# schematic.net
KiCad netlist of a schematic drawn in EasyEDA
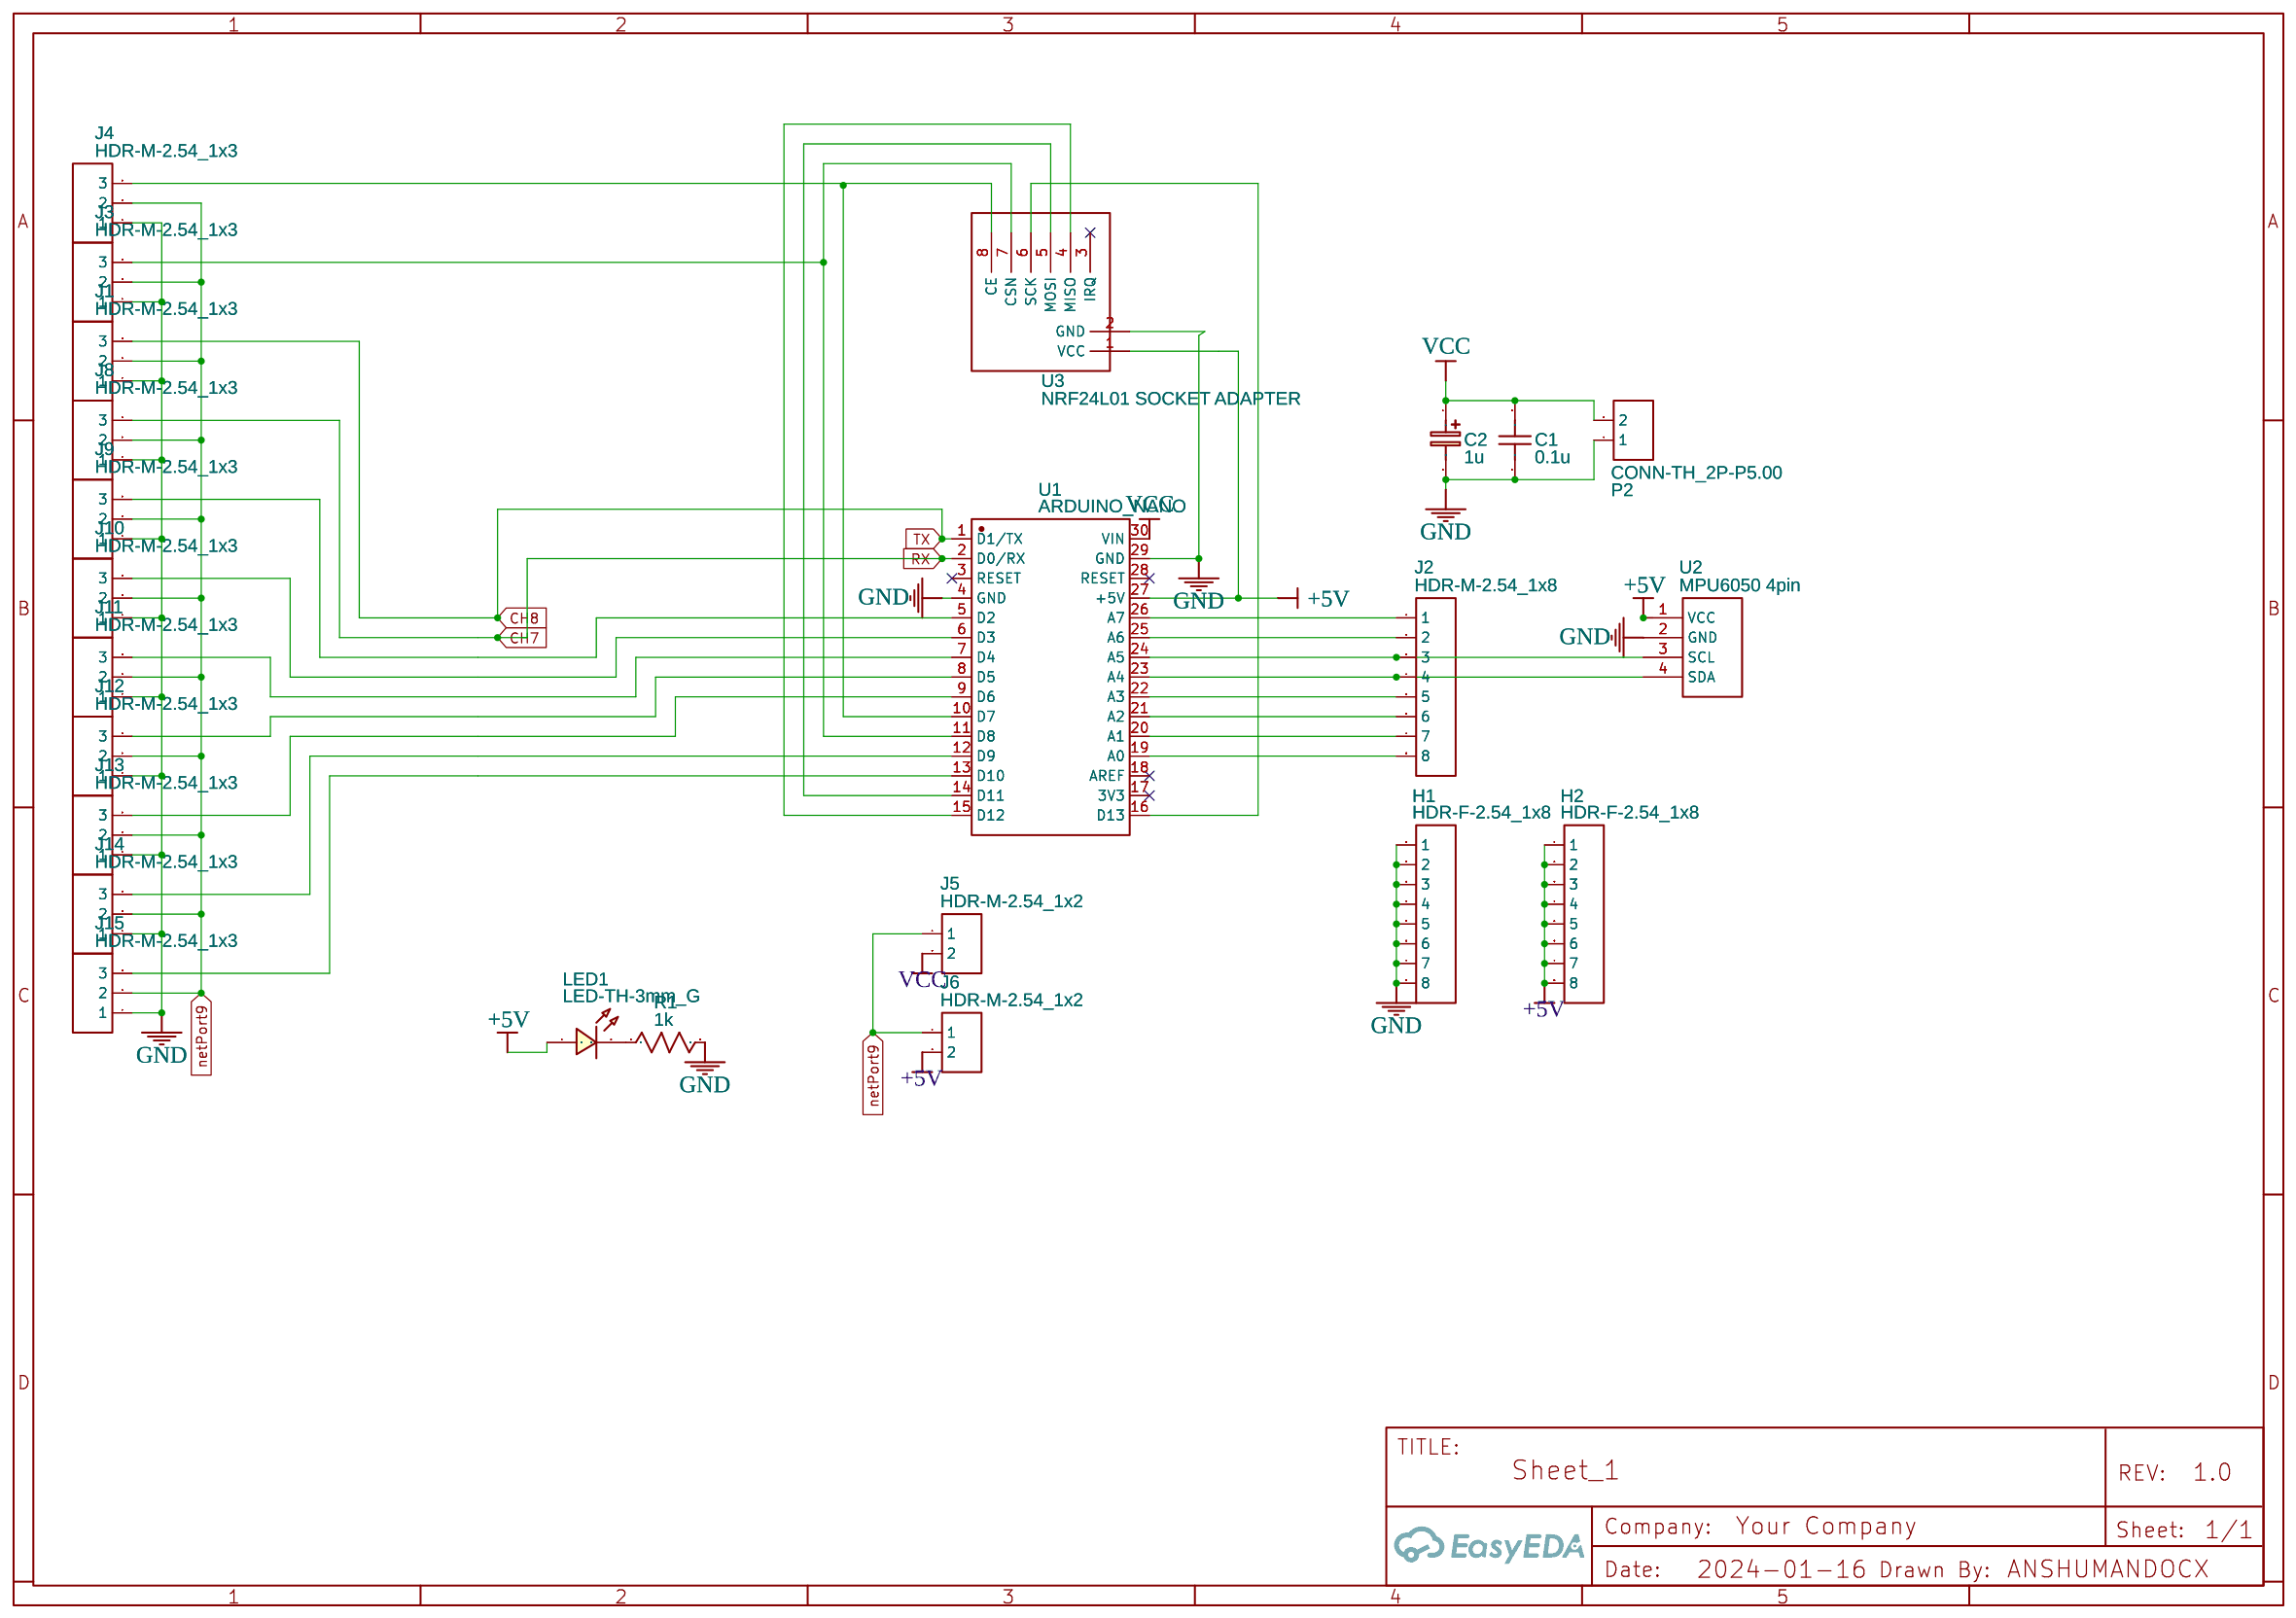
[diagram p0: schematic sheet]

(export (version "E")
  (design (tool "Eeschema 10.0.6"))
  (components
    (comp (ref "C1") (value "0.1u") (libsource (lib "") (part "C_0805_US")))
    (comp (ref "C2") (value "1u") (libsource (lib "") (part "CE_TH_D5.0×F2.0_EU")))
    (comp (ref "H1") (value "HDR-F-2.54_1x8") (libsource (lib "") (part "HDR-F-2.54_1x8")))
    (comp (ref "H2") (value "HDR-F-2.54_1x8") (libsource (lib "") (part "HDR-F-2.54_1x8")))
    (comp (ref "J1") (value "HDR-M-2.54_1x3") (libsource (lib "") (part "HDR-M-2.54_1x3")))
    (comp (ref "J2") (value "HDR-M-2.54_1x8") (libsource (lib "") (part "HDR-M-2.54_1x8")))
    (comp (ref "J3") (value "HDR-M-2.54_1x3") (libsource (lib "") (part "HDR-M-2.54_1x3")))
    (comp (ref "J4") (value "HDR-M-2.54_1x3") (libsource (lib "") (part "HDR-M-2.54_1x3")))
    (comp (ref "J5") (value "HDR-M-2.54_1x2") (libsource (lib "") (part "HDR-M-2.54_1x2")))
    (comp (ref "J6") (value "HDR-M-2.54_1x2") (libsource (lib "") (part "HDR-M-2.54_1x2")))
    (comp (ref "J8") (value "HDR-M-2.54_1x3") (libsource (lib "") (part "HDR-M-2.54_1x3")))
    (comp (ref "J9") (value "HDR-M-2.54_1x3") (libsource (lib "") (part "HDR-M-2.54_1x3")))
    (comp (ref "J10") (value "HDR-M-2.54_1x3") (libsource (lib "") (part "HDR-M-2.54_1x3")))
    (comp (ref "J11") (value "HDR-M-2.54_1x3") (libsource (lib "") (part "HDR-M-2.54_1x3")))
    (comp (ref "J12") (value "HDR-M-2.54_1x3") (libsource (lib "") (part "HDR-M-2.54_1x3")))
    (comp (ref "J13") (value "HDR-M-2.54_1x3") (libsource (lib "") (part "HDR-M-2.54_1x3")))
    (comp (ref "J14") (value "HDR-M-2.54_1x3") (libsource (lib "") (part "HDR-M-2.54_1x3")))
    (comp (ref "J15") (value "HDR-M-2.54_1x3") (libsource (lib "") (part "HDR-M-2.54_1x3")))
    (comp (ref "LED1")
      (value "LED-TH-3mm_G")
      (fields
        (field (name "Manufacturer Part") "204-10SYGD/S530-E3")
        (field (name "Manufacturer") "EVERLIGHT(台湾亿光)")
      )
      (libsource (lib "") (part "LED-TH-3mm_G"))
    )
    (comp (ref "P2") (value "CONN-TH_2P-P5.00") (libsource (lib "") (part "CONN-TH_2P-P5.00")))
    (comp (ref "R1") (value "1k") (libsource (lib "") (part "R_AXIAL-0.4_US")))
    (comp (ref "U1") (value "ARDUINO_NANO") (libsource (lib "") (part "ARDUINO_NANO")))
    (comp (ref "U2") (value "MPU6050 4pin") (libsource (lib "") (part "MPU6050 4pin")))
    (comp (ref "U3") (value "NRF24L01 SOCKET ADAPTER") (libsource (lib "") (part "NRF24L01 SOCKET ADAPTER")))
  )
  (nets
    (net (code "1") (name "+5V") (class "Default")
      (node (ref "H2") (pin "1") (pinfunction "1_1") (pintype "unspecified"))
      (node (ref "H2") (pin "2") (pinfunction "2_2") (pintype "unspecified"))
      (node (ref "H2") (pin "3") (pinfunction "3_3") (pintype "unspecified"))
      (node (ref "H2") (pin "4") (pinfunction "4_4") (pintype "unspecified"))
      (node (ref "H2") (pin "5") (pinfunction "5_5") (pintype "unspecified"))
      (node (ref "H2") (pin "6") (pinfunction "6_6") (pintype "unspecified"))
      (node (ref "H2") (pin "7") (pinfunction "7_7") (pintype "unspecified"))
      (node (ref "H2") (pin "8") (pinfunction "8_8") (pintype "unspecified"))
      (node (ref "J6") (pin "2") (pinfunction "2_2") (pintype "unspecified"))
      (node (ref "LED1") (pin "1") (pinfunction "1_1") (pintype "unspecified"))
      (node (ref "U1") (pin "27") (pinfunction "+5V_27") (pintype "unspecified"))
      (node (ref "U2") (pin "1") (pinfunction "VCC_1") (pintype "unspecified"))
      (node (ref "U3") (pin "1") (pinfunction "VCC_1") (pintype "unspecified"))
    )
    (net (code "2") (name "CH7") (class "Default")
      (node (ref "J8") (pin "3") (pinfunction "3_3") (pintype "input"))
      (node (ref "U1") (pin "2") (pinfunction "D0/RX_2") (pintype "unspecified"))
    )
    (net (code "3") (name "CH8") (class "Default")
      (node (ref "J1") (pin "3") (pinfunction "3_3") (pintype "input"))
      (node (ref "U1") (pin "1") (pinfunction "D1/TX_1") (pintype "unspecified"))
    )
    (net (code "4") (name "GND") (class "Default")
      (node (ref "C1") (pin "1") (pinfunction "1_1") (pintype "unspecified"))
      (node (ref "C2") (pin "2") (pinfunction "2_2") (pintype "unspecified"))
      (node (ref "H1") (pin "1") (pinfunction "1_1") (pintype "unspecified"))
      (node (ref "H1") (pin "2") (pinfunction "2_2") (pintype "unspecified"))
      (node (ref "H1") (pin "3") (pinfunction "3_3") (pintype "unspecified"))
      (node (ref "H1") (pin "4") (pinfunction "4_4") (pintype "unspecified"))
      (node (ref "H1") (pin "5") (pinfunction "5_5") (pintype "unspecified"))
      (node (ref "H1") (pin "6") (pinfunction "6_6") (pintype "unspecified"))
      (node (ref "H1") (pin "7") (pinfunction "7_7") (pintype "unspecified"))
      (node (ref "H1") (pin "8") (pinfunction "8_8") (pintype "unspecified"))
      (node (ref "J1") (pin "1") (pinfunction "1_1") (pintype "input"))
      (node (ref "J10") (pin "1") (pinfunction "1_1") (pintype "input"))
      (node (ref "J11") (pin "1") (pinfunction "1_1") (pintype "input"))
      (node (ref "J12") (pin "1") (pinfunction "1_1") (pintype "input"))
      (node (ref "J13") (pin "1") (pinfunction "1_1") (pintype "input"))
      (node (ref "J14") (pin "1") (pinfunction "1_1") (pintype "input"))
      (node (ref "J15") (pin "1") (pinfunction "1_1") (pintype "input"))
      (node (ref "J3") (pin "1") (pinfunction "1_1") (pintype "input"))
      (node (ref "J4") (pin "1") (pinfunction "1_1") (pintype "input"))
      (node (ref "J8") (pin "1") (pinfunction "1_1") (pintype "input"))
      (node (ref "J9") (pin "1") (pinfunction "1_1") (pintype "input"))
      (node (ref "P2") (pin "1") (pinfunction "1_1") (pintype "unspecified"))
      (node (ref "R1") (pin "2") (pinfunction "2_2") (pintype "unspecified"))
      (node (ref "U1") (pin "29") (pinfunction "GND_29") (pintype "unspecified"))
      (node (ref "U1") (pin "4") (pinfunction "GND_4") (pintype "unspecified"))
      (node (ref "U2") (pin "2") (pinfunction "GND_2") (pintype "unspecified"))
      (node (ref "U3") (pin "2") (pinfunction "GND_2") (pintype "unspecified"))
    )
    (net (code "5") (name "Net-(LED1-Pad2)") (class "Default")
      (node (ref "LED1") (pin "2") (pinfunction "2_2") (pintype "unspecified"))
      (node (ref "R1") (pin "1") (pinfunction "1_1") (pintype "unspecified"))
    )
    (net (code "6") (name "Net-(U1-A0)") (class "Default")
      (node (ref "J2") (pin "8") (pinfunction "8_8") (pintype "unspecified"))
      (node (ref "U1") (pin "19") (pinfunction "A0_19") (pintype "unspecified"))
    )
    (net (code "7") (name "Net-(U1-A1)") (class "Default")
      (node (ref "J2") (pin "7") (pinfunction "7_7") (pintype "unspecified"))
      (node (ref "U1") (pin "20") (pinfunction "A1_20") (pintype "unspecified"))
    )
    (net (code "8") (name "Net-(U1-A2)") (class "Default")
      (node (ref "J2") (pin "6") (pinfunction "6_6") (pintype "unspecified"))
      (node (ref "U1") (pin "21") (pinfunction "A2_21") (pintype "unspecified"))
    )
    (net (code "9") (name "Net-(U1-A3)") (class "Default")
      (node (ref "J2") (pin "5") (pinfunction "5_5") (pintype "unspecified"))
      (node (ref "U1") (pin "22") (pinfunction "A3_22") (pintype "unspecified"))
    )
    (net (code "10") (name "Net-(U1-A4)") (class "Default")
      (node (ref "J2") (pin "4") (pinfunction "4_4") (pintype "unspecified"))
      (node (ref "U1") (pin "23") (pinfunction "A4_23") (pintype "unspecified"))
      (node (ref "U2") (pin "4") (pinfunction "SDA_4") (pintype "unspecified"))
    )
    (net (code "11") (name "Net-(U1-A5)") (class "Default")
      (node (ref "J2") (pin "3") (pinfunction "3_3") (pintype "unspecified"))
      (node (ref "U1") (pin "24") (pinfunction "A5_24") (pintype "unspecified"))
      (node (ref "U2") (pin "3") (pinfunction "SCL_3") (pintype "unspecified"))
    )
    (net (code "12") (name "Net-(U1-A6)") (class "Default")
      (node (ref "J2") (pin "2") (pinfunction "2_2") (pintype "unspecified"))
      (node (ref "U1") (pin "25") (pinfunction "A6_25") (pintype "unspecified"))
    )
    (net (code "13") (name "Net-(U1-A7)") (class "Default")
      (node (ref "J2") (pin "1") (pinfunction "1_1") (pintype "unspecified"))
      (node (ref "U1") (pin "26") (pinfunction "A7_26") (pintype "unspecified"))
    )
    (net (code "14") (name "Net-(U1-D2)") (class "Default")
      (node (ref "J9") (pin "3") (pinfunction "3_3") (pintype "input"))
      (node (ref "U1") (pin "5") (pinfunction "D2_5") (pintype "unspecified"))
    )
    (net (code "15") (name "Net-(U1-D3)") (class "Default")
      (node (ref "J10") (pin "3") (pinfunction "3_3") (pintype "input"))
      (node (ref "U1") (pin "6") (pinfunction "D3_6") (pintype "unspecified"))
    )
    (net (code "16") (name "Net-(U1-D4)") (class "Default")
      (node (ref "J11") (pin "3") (pinfunction "3_3") (pintype "input"))
      (node (ref "U1") (pin "7") (pinfunction "D4_7") (pintype "unspecified"))
    )
    (net (code "17") (name "Net-(U1-D5)") (class "Default")
      (node (ref "J12") (pin "3") (pinfunction "3_3") (pintype "input"))
      (node (ref "U1") (pin "8") (pinfunction "D5_8") (pintype "unspecified"))
    )
    (net (code "18") (name "Net-(U1-D6)") (class "Default")
      (node (ref "J13") (pin "3") (pinfunction "3_3") (pintype "input"))
      (node (ref "U1") (pin "9") (pinfunction "D6_9") (pintype "unspecified"))
    )
    (net (code "19") (name "Net-(U1-D7)") (class "Default")
      (node (ref "J4") (pin "3") (pinfunction "3_3") (pintype "input"))
      (node (ref "U1") (pin "10") (pinfunction "D7_10") (pintype "unspecified"))
      (node (ref "U3") (pin "8") (pinfunction "CE_8") (pintype "unspecified"))
    )
    (net (code "20") (name "Net-(U1-D8)") (class "Default")
      (node (ref "J3") (pin "3") (pinfunction "3_3") (pintype "input"))
      (node (ref "U1") (pin "11") (pinfunction "D8_11") (pintype "unspecified"))
      (node (ref "U3") (pin "7") (pinfunction "CSN_7") (pintype "unspecified"))
    )
    (net (code "21") (name "Net-(U1-D9)") (class "Default")
      (node (ref "J14") (pin "3") (pinfunction "3_3") (pintype "input"))
      (node (ref "U1") (pin "12") (pinfunction "D9_12") (pintype "unspecified"))
    )
    (net (code "22") (name "Net-(U1-D10)") (class "Default")
      (node (ref "J15") (pin "3") (pinfunction "3_3") (pintype "input"))
      (node (ref "U1") (pin "13") (pinfunction "D10_13") (pintype "unspecified"))
    )
    (net (code "23") (name "Net-(U1-D11)") (class "Default")
      (node (ref "U1") (pin "14") (pinfunction "D11_14") (pintype "unspecified"))
      (node (ref "U3") (pin "5") (pinfunction "MOSI_5") (pintype "unspecified"))
    )
    (net (code "24") (name "Net-(U1-D12)") (class "Default")
      (node (ref "U1") (pin "15") (pinfunction "D12_15") (pintype "unspecified"))
      (node (ref "U3") (pin "4") (pinfunction "MISO_4") (pintype "unspecified"))
    )
    (net (code "25") (name "Net-(U1-D13)") (class "Default")
      (node (ref "U1") (pin "16") (pinfunction "D13_16") (pintype "unspecified"))
      (node (ref "U3") (pin "6") (pinfunction "SCK_6") (pintype "unspecified"))
    )
    (net (code "26") (name "VCC") (class "Default")
      (node (ref "C1") (pin "2") (pinfunction "2_2") (pintype "unspecified"))
      (node (ref "C2") (pin "1") (pinfunction "1_1") (pintype "unspecified"))
      (node (ref "J5") (pin "2") (pinfunction "2_2") (pintype "unspecified"))
      (node (ref "P2") (pin "2") (pinfunction "2_2") (pintype "unspecified"))
      (node (ref "U1") (pin "30") (pinfunction "VIN_30") (pintype "unspecified"))
    )
    (net (code "27") (name "netPort9") (class "Default")
      (node (ref "J1") (pin "2") (pinfunction "2_2") (pintype "input"))
      (node (ref "J10") (pin "2") (pinfunction "2_2") (pintype "input"))
      (node (ref "J11") (pin "2") (pinfunction "2_2") (pintype "input"))
      (node (ref "J12") (pin "2") (pinfunction "2_2") (pintype "input"))
      (node (ref "J13") (pin "2") (pinfunction "2_2") (pintype "input"))
      (node (ref "J14") (pin "2") (pinfunction "2_2") (pintype "input"))
      (node (ref "J15") (pin "2") (pinfunction "2_2") (pintype "input"))
      (node (ref "J3") (pin "2") (pinfunction "2_2") (pintype "input"))
      (node (ref "J4") (pin "2") (pinfunction "2_2") (pintype "input"))
      (node (ref "J5") (pin "1") (pinfunction "1_1") (pintype "unspecified"))
      (node (ref "J6") (pin "1") (pinfunction "1_1") (pintype "unspecified"))
      (node (ref "J8") (pin "2") (pinfunction "2_2") (pintype "input"))
      (node (ref "J9") (pin "2") (pinfunction "2_2") (pintype "input"))
    )
    (net (code "28") (name "unconnected-(U1-3V3-Pad17)") (class "Default")
      (node (ref "U1") (pin "17") (pinfunction "3V3_17") (pintype "unspecified+no_connect"))
    )
    (net (code "29") (name "unconnected-(U1-AREF-Pad18)") (class "Default")
      (node (ref "U1") (pin "18") (pinfunction "AREF_18") (pintype "unspecified+no_connect"))
    )
    (net (code "30") (name "unconnected-(U1-RESET-Pad3)") (class "Default")
      (node (ref "U1") (pin "3") (pinfunction "RESET_3") (pintype "unspecified+no_connect"))
    )
    (net (code "31") (name "unconnected-(U1-RESET-Pad28)") (class "Default")
      (node (ref "U1") (pin "28") (pinfunction "RESET_28") (pintype "unspecified+no_connect"))
    )
    (net (code "32") (name "unconnected-(U3-IRQ-Pad3)") (class "Default")
      (node (ref "U3") (pin "3") (pinfunction "IRQ_3") (pintype "unspecified+no_connect"))
    )
  )
)
